# digit_3.net
KiCad netlist of a schematic drawn in EAGLE
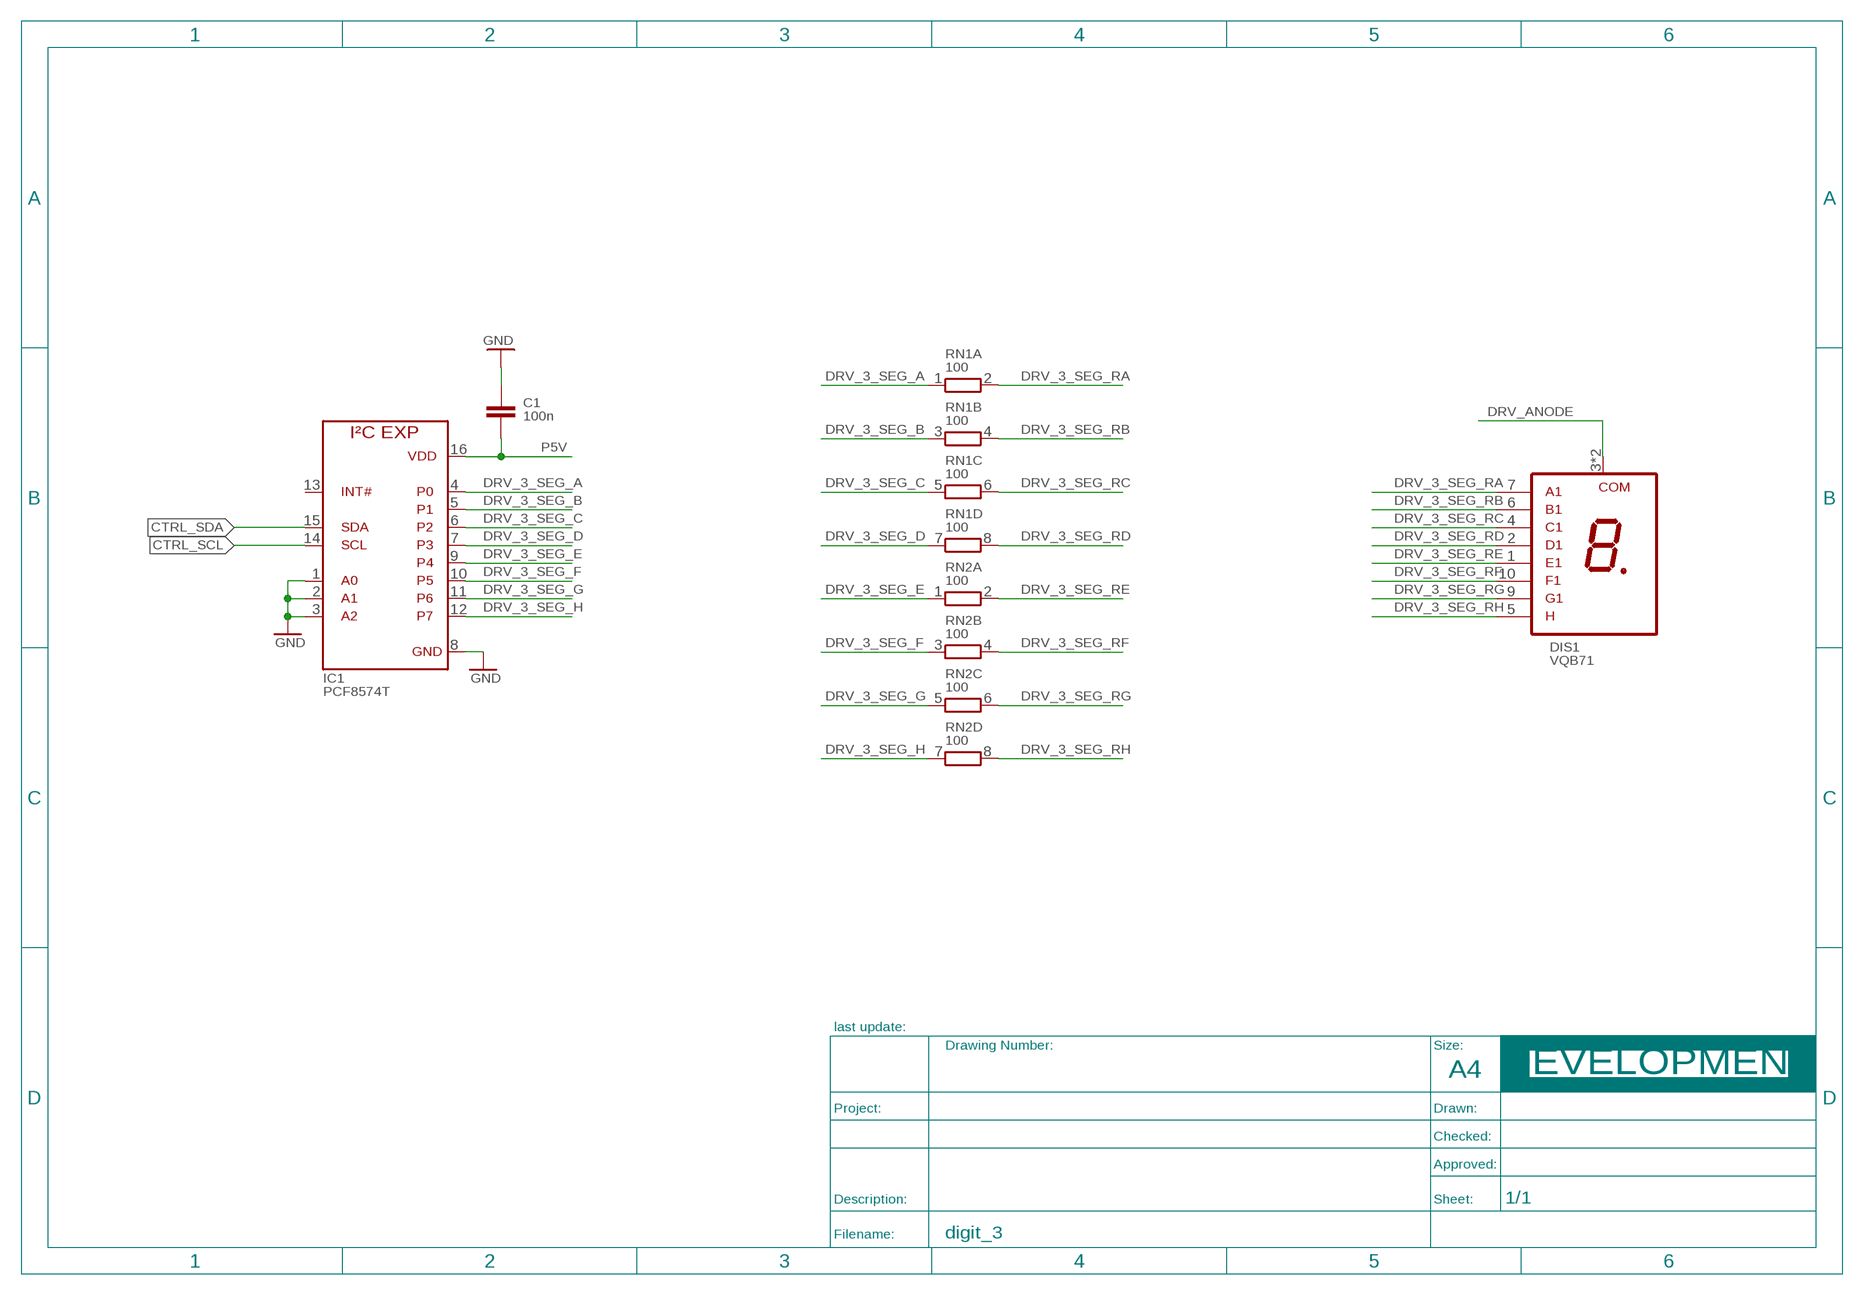
[diagram p0: schematic, sheet 1]

(export (version "E")
  (design (tool "Eeschema 10.0.6"))
  (components
    (comp (ref "C1")
      (value "100n")
      (footprint "eagle-import:S_0805")
      (fields (field (name "PART_CODE_BEL") "C_PAC_S_0805_VAL_100n"))
      (libsource (lib "eagle-import") (part "C_EU_S_0805"))
    )
    (comp (ref "DIS1")
      (value "VQB71")
      (footprint "eagle-import:T_VQB71")
      (libsource (lib "eagle-import") (part "VQB71"))
    )
    (comp (ref "IC1")
      (value "PCF8574T")
      (footprint "eagle-import:S_SOIC16")
      (libsource (lib "eagle-import") (part "PCF8574T"))
    )
    (comp (ref "RN1")
      (value "100")
      (footprint "eagle-import:T_SIL8")
      (fields (field (name "PART_CODE_BEL") "RN_PAC_T_SIL8_VAL_100"))
      (libsource (lib "eagle-import") (part "R_EU_ARRAY_4"))
    )
    (comp (ref "RN2")
      (value "100")
      (footprint "eagle-import:T_SIL8")
      (fields (field (name "PART_CODE_BEL") "RN_PAC_T_SIL8_VAL_100"))
      (libsource (lib "eagle-import") (part "R_EU_ARRAY_4"))
    )
  )
  (nets
    (net (code "1") (name "/DRV_3_SEG_A") (class "Default")
      (node (ref "IC1") (pin "4") (pinfunction "P0_4") (pintype "bidirectional"))
      (node (ref "RN1") (pin "1") (pinfunction "1_1") (pintype "passive"))
    )
    (net (code "2") (name "/DRV_3_SEG_B") (class "Default")
      (node (ref "IC1") (pin "5") (pinfunction "P1_5") (pintype "bidirectional"))
      (node (ref "RN1") (pin "3") (pinfunction "1_3") (pintype "passive"))
    )
    (net (code "3") (name "/DRV_3_SEG_C") (class "Default")
      (node (ref "IC1") (pin "6") (pinfunction "P2_6") (pintype "bidirectional"))
      (node (ref "RN1") (pin "5") (pinfunction "1_5") (pintype "passive"))
    )
    (net (code "4") (name "/DRV_3_SEG_D") (class "Default")
      (node (ref "IC1") (pin "7") (pinfunction "P3_7") (pintype "bidirectional"))
      (node (ref "RN1") (pin "7") (pinfunction "1_7") (pintype "passive"))
    )
    (net (code "5") (name "/DRV_3_SEG_E") (class "Default")
      (node (ref "IC1") (pin "9") (pinfunction "P4_9") (pintype "bidirectional"))
      (node (ref "RN2") (pin "1") (pinfunction "1_1") (pintype "passive"))
    )
    (net (code "6") (name "/DRV_3_SEG_F") (class "Default")
      (node (ref "IC1") (pin "10") (pinfunction "P5_10") (pintype "bidirectional"))
      (node (ref "RN2") (pin "3") (pinfunction "1_3") (pintype "passive"))
    )
    (net (code "7") (name "/DRV_3_SEG_G") (class "Default")
      (node (ref "IC1") (pin "11") (pinfunction "P6_11") (pintype "bidirectional"))
      (node (ref "RN2") (pin "5") (pinfunction "1_5") (pintype "passive"))
    )
    (net (code "8") (name "/DRV_3_SEG_H") (class "Default")
      (node (ref "IC1") (pin "12") (pinfunction "P7_12") (pintype "bidirectional"))
      (node (ref "RN2") (pin "7") (pinfunction "1_7") (pintype "passive"))
    )
    (net (code "9") (name "/DRV_3_SEG_RA") (class "Default")
      (node (ref "DIS1") (pin "7") (pinfunction "A1_7") (pintype "passive"))
      (node (ref "RN1") (pin "2") (pinfunction "2_2") (pintype "passive"))
    )
    (net (code "10") (name "/DRV_3_SEG_RB") (class "Default")
      (node (ref "DIS1") (pin "6") (pinfunction "B1_6") (pintype "passive"))
      (node (ref "RN1") (pin "4") (pinfunction "2_4") (pintype "passive"))
    )
    (net (code "11") (name "/DRV_3_SEG_RC") (class "Default")
      (node (ref "DIS1") (pin "4") (pinfunction "C1_4") (pintype "passive"))
      (node (ref "RN1") (pin "6") (pinfunction "2_6") (pintype "passive"))
    )
    (net (code "12") (name "/DRV_3_SEG_RD") (class "Default")
      (node (ref "DIS1") (pin "2") (pinfunction "D1_2") (pintype "passive"))
      (node (ref "RN1") (pin "8") (pinfunction "2_8") (pintype "passive"))
    )
    (net (code "13") (name "/DRV_3_SEG_RE") (class "Default")
      (node (ref "DIS1") (pin "1") (pinfunction "E1_1") (pintype "passive"))
      (node (ref "RN2") (pin "2") (pinfunction "2_2") (pintype "passive"))
    )
    (net (code "14") (name "/DRV_3_SEG_RF") (class "Default")
      (node (ref "DIS1") (pin "10") (pinfunction "F1_10") (pintype "passive"))
      (node (ref "RN2") (pin "4") (pinfunction "2_4") (pintype "passive"))
    )
    (net (code "15") (name "/DRV_3_SEG_RG") (class "Default")
      (node (ref "DIS1") (pin "9") (pinfunction "G1_9") (pintype "passive"))
      (node (ref "RN2") (pin "6") (pinfunction "2_6") (pintype "passive"))
    )
    (net (code "16") (name "/DRV_3_SEG_RH") (class "Default")
      (node (ref "DIS1") (pin "5") (pinfunction "DP1_5") (pintype "passive"))
      (node (ref "RN2") (pin "8") (pinfunction "2_8") (pintype "passive"))
    )
    (net (code "17") (name "/DRV_ANODE") (class "Default")
      (node (ref "DIS1") (pin "3") (pinfunction "COM1_3") (pintype "passive"))
      (node (ref "DIS1") (pin "8") (pinfunction "COM1_8") (pintype "passive"))
    )
    (net (code "18") (name "/P5V") (class "Default")
      (node (ref "C1") (pin "2") (pinfunction "2_2") (pintype "passive"))
      (node (ref "IC1") (pin "16") (pinfunction "VDD_16") (pintype "power_in"))
    )
    (net (code "19") (name "CTRL_SCL") (class "Default")
      (node (ref "IC1") (pin "14") (pinfunction "SCL_14") (pintype "input"))
    )
    (net (code "20") (name "CTRL_SDA") (class "Default")
      (node (ref "IC1") (pin "15") (pinfunction "SDA_15") (pintype "bidirectional"))
    )
    (net (code "21") (name "GND") (class "Default")
      (node (ref "C1") (pin "1") (pinfunction "1_1") (pintype "passive"))
      (node (ref "IC1") (pin "1") (pinfunction "A0_1") (pintype "input"))
      (node (ref "IC1") (pin "2") (pinfunction "A1_2") (pintype "input"))
      (node (ref "IC1") (pin "3") (pinfunction "A2_3") (pintype "input"))
      (node (ref "IC1") (pin "8") (pinfunction "GND_8") (pintype "power_in"))
    )
    (net (code "22") (name "unconnected-(IC1-~{INT}-Pad13)") (class "Default")
      (node (ref "IC1") (pin "13") (pinfunction "~{INT}_13") (pintype "output"))
    )
  )
)
